# Escorna_CPU_2_01.net
KiCad netlist of a schematic drawn in EAGLE
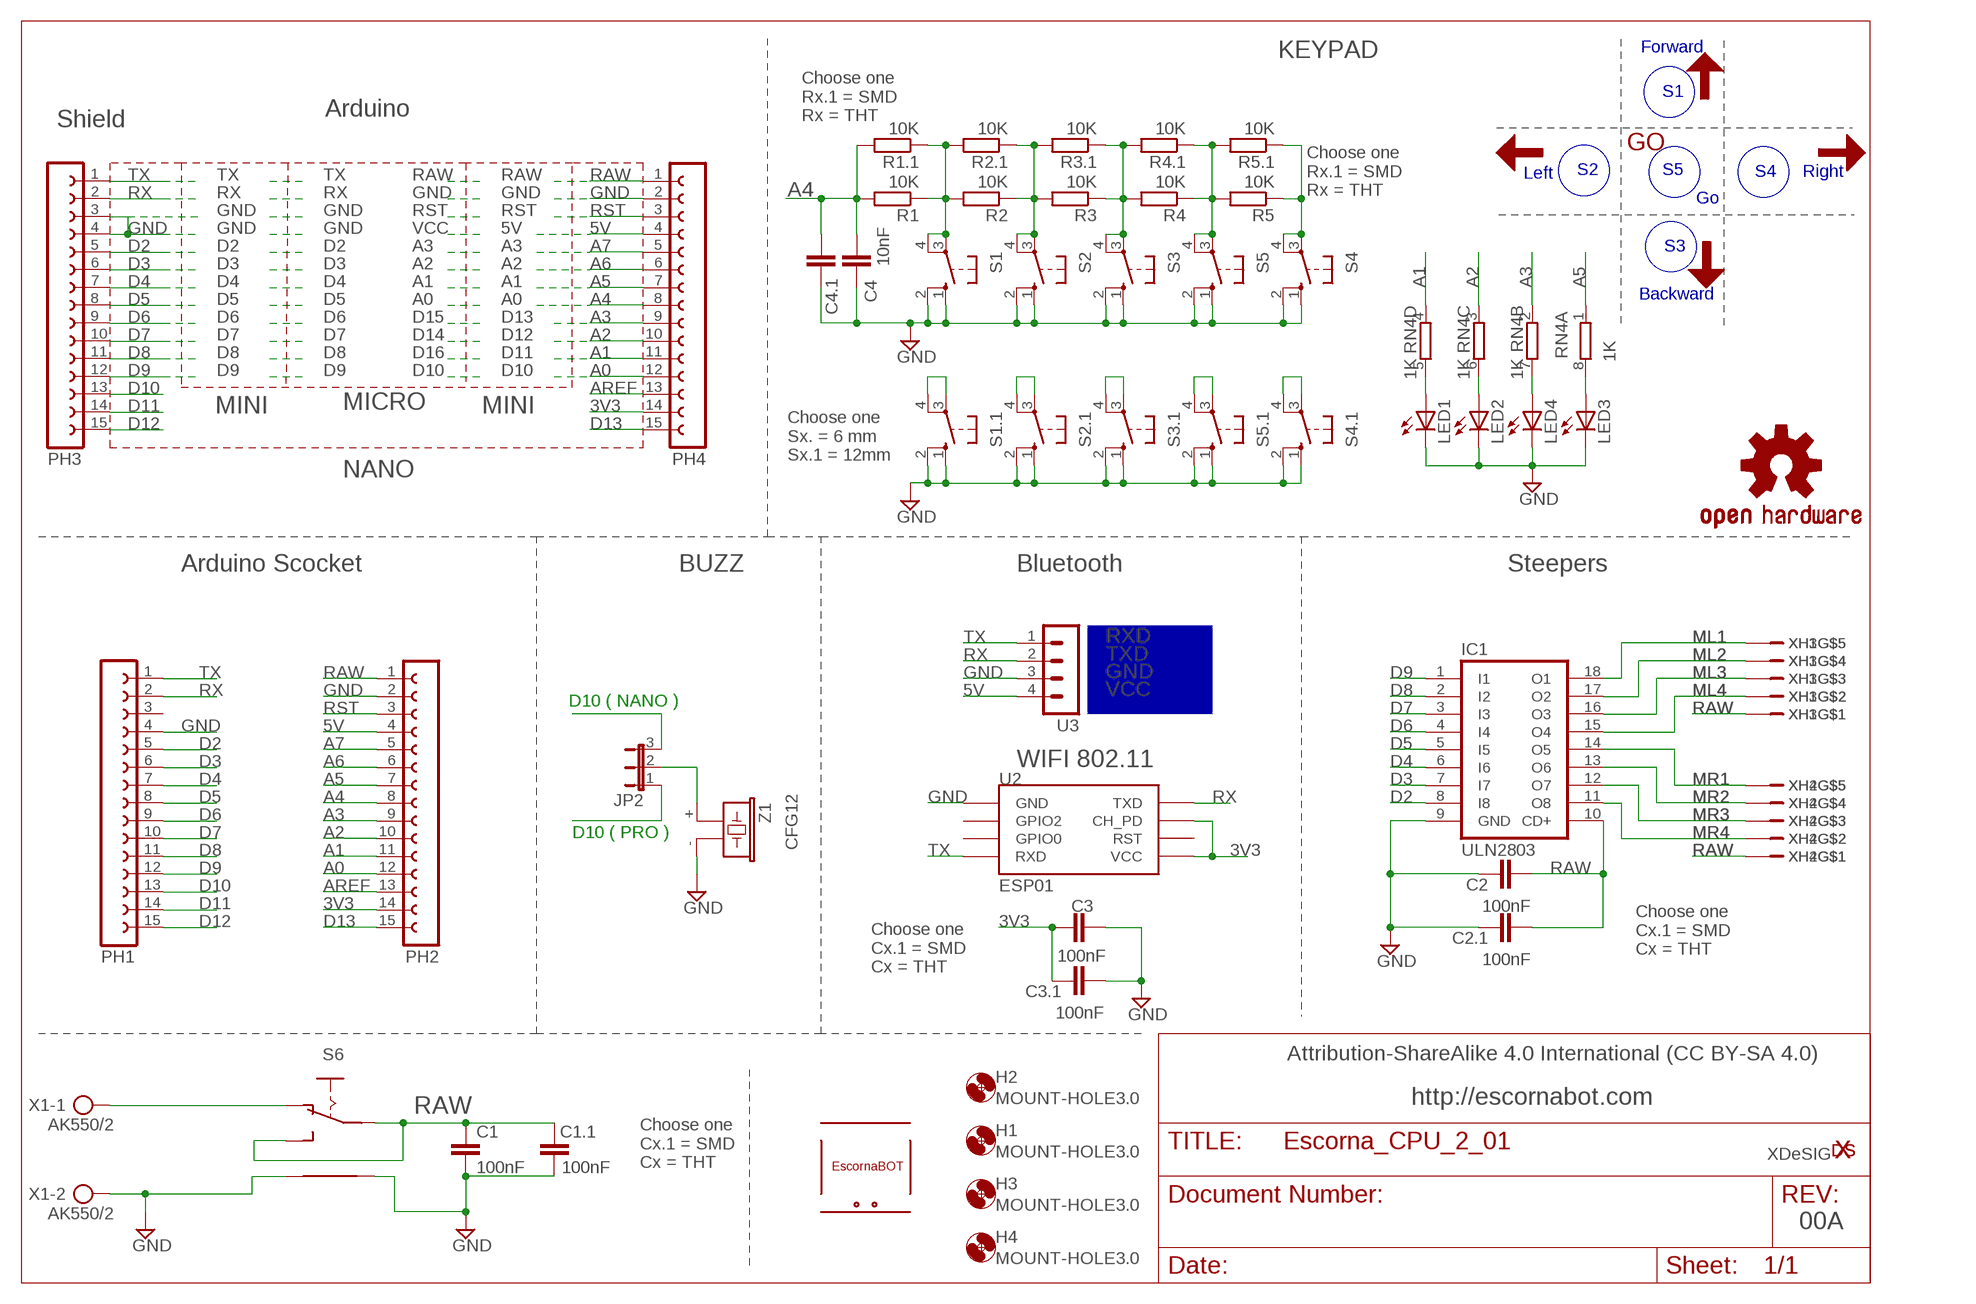
[diagram p0: schematic, sheet 1]

(export (version "E")
  (design (tool "Eeschema 10.0.6"))
  (components
    (comp (ref "C1")
      (value "100nF")
      (footprint "eagle-import:C025-025X050")
      (libsource (lib "eagle-import") (part "C-EU025-025X050"))
    )
    (comp (ref "C1.1")
      (value "100nF")
      (footprint "eagle-import:C0603")
      (libsource (lib "eagle-import") (part "C-EUC0603"))
    )
    (comp (ref "C2")
      (value "100nF")
      (footprint "eagle-import:C025-025X050")
      (libsource (lib "eagle-import") (part "C-EU025-025X050"))
    )
    (comp (ref "C2.1")
      (value "100nF")
      (footprint "eagle-import:C0603")
      (libsource (lib "eagle-import") (part "C-EUC0603"))
    )
    (comp (ref "C3")
      (value "100nF")
      (footprint "eagle-import:C025-025X050")
      (libsource (lib "eagle-import") (part "C-EU025-025X050"))
    )
    (comp (ref "C3.1")
      (value "100nF")
      (footprint "eagle-import:C0603")
      (libsource (lib "eagle-import") (part "C-EUC0603"))
    )
    (comp (ref "C4")
      (value "10nF")
      (footprint "eagle-import:C025-025X050")
      (libsource (lib "eagle-import") (part "C-EU025-025X050"))
    )
    (comp (ref "C4.1")
      (value "10nF")
      (footprint "eagle-import:C0603")
      (libsource (lib "eagle-import") (part "C-EUC0603"))
    )
    (comp (ref "ESC")
      (value "ESCORNABOT")
      (footprint "eagle-import:ESCORNA_PEQUE")
      (libsource (lib "eagle-import") (part "ESCORNABOT"))
    )
    (comp (ref "H1")
      (value "MOUNT-HOLE3.0")
      (footprint "eagle-import:3,0")
      (libsource (lib "eagle-import") (part "MOUNT-HOLE3.0"))
    )
    (comp (ref "H2")
      (value "MOUNT-HOLE3.0")
      (footprint "eagle-import:3,0")
      (libsource (lib "eagle-import") (part "MOUNT-HOLE3.0"))
    )
    (comp (ref "H3")
      (value "MOUNT-HOLE3.0")
      (footprint "eagle-import:3,0")
      (libsource (lib "eagle-import") (part "MOUNT-HOLE3.0"))
    )
    (comp (ref "H4")
      (value "MOUNT-HOLE3.0")
      (footprint "eagle-import:3,0")
      (libsource (lib "eagle-import") (part "MOUNT-HOLE3.0"))
    )
    (comp (ref "IC1")
      (value "ULN2803")
      (footprint "eagle-import:DIL18")
      (libsource (lib "eagle-import") (part "ULN2803A{dblquote}"))
    )
    (comp (ref "JP2")
      (value "JP2E")
      (footprint "eagle-import:JP2")
      (libsource (lib "eagle-import") (part "JP2E"))
    )
    (comp (ref "LED1")
      (value "LED_ESML0603")
      (footprint "eagle-import:LED_SML0603")
      (libsource (lib "eagle-import") (part "LED_ESML0603"))
    )
    (comp (ref "LED2")
      (value "LED_ESML0603")
      (footprint "eagle-import:LED_SML0603")
      (libsource (lib "eagle-import") (part "LED_ESML0603"))
    )
    (comp (ref "LED3")
      (value "LED_ESML0603")
      (footprint "eagle-import:LED_SML0603")
      (libsource (lib "eagle-import") (part "LED_ESML0603"))
    )
    (comp (ref "LED4")
      (value "LED_ESML0603")
      (footprint "eagle-import:LED_SML0603")
      (libsource (lib "eagle-import") (part "LED_ESML0603"))
    )
    (comp (ref "LOGO2")
      (value "OSHW-LOGOS")
      (footprint "eagle-import:OSHW-LOGO-S")
      (libsource (lib "eagle-import") (part "OSHW-LOGOS"))
    )
    (comp (ref "PH1")
      (value "FE15-1")
      (footprint "eagle-import:FE15")
      (libsource (lib "eagle-import") (part "FE15-1"))
    )
    (comp (ref "PH2")
      (value "FE15-1")
      (footprint "eagle-import:FE15")
      (libsource (lib "eagle-import") (part "FE15-1"))
    )
    (comp (ref "PH3")
      (value "FE15-1")
      (footprint "eagle-import:FE15")
      (libsource (lib "eagle-import") (part "FE15-1"))
    )
    (comp (ref "PH4")
      (value "FE15-1")
      (footprint "eagle-import:FE15")
      (libsource (lib "eagle-import") (part "FE15-1"))
    )
    (comp (ref "R1")
      (value "10K")
      (footprint "eagle-import:0204_7")
      (libsource (lib "eagle-import") (part "R-EU_0204/7"))
    )
    (comp (ref "R1.1")
      (value "10K")
      (footprint "eagle-import:R0603")
      (libsource (lib "eagle-import") (part "R-EU_R0603"))
    )
    (comp (ref "R2")
      (value "10K")
      (footprint "eagle-import:0204_7")
      (libsource (lib "eagle-import") (part "R-EU_0204/7"))
    )
    (comp (ref "R2.1")
      (value "10K")
      (footprint "eagle-import:R0603")
      (libsource (lib "eagle-import") (part "R-EU_R0603"))
    )
    (comp (ref "R3")
      (value "10K")
      (footprint "eagle-import:0204_7")
      (libsource (lib "eagle-import") (part "R-EU_0204/7"))
    )
    (comp (ref "R3.1")
      (value "10K")
      (footprint "eagle-import:R0603")
      (libsource (lib "eagle-import") (part "R-EU_R0603"))
    )
    (comp (ref "R4")
      (value "10K")
      (footprint "eagle-import:0204_7")
      (libsource (lib "eagle-import") (part "R-EU_0204/7"))
    )
    (comp (ref "R4.1")
      (value "10K")
      (footprint "eagle-import:R0603")
      (libsource (lib "eagle-import") (part "R-EU_R0603"))
    )
    (comp (ref "R5")
      (value "10K")
      (footprint "eagle-import:0204_7")
      (libsource (lib "eagle-import") (part "R-EU_0204/7"))
    )
    (comp (ref "R5.1")
      (value "10K")
      (footprint "eagle-import:R0603")
      (libsource (lib "eagle-import") (part "R-EU_R0603"))
    )
    (comp (ref "RN4")
      (value "1K")
      (footprint "eagle-import:CAY16")
      (libsource (lib "eagle-import") (part "4R-NCAY16"))
    )
    (comp (ref "S1")
      (value "10-XX")
      (footprint "eagle-import:B3F-10XX")
      (fields (field (name "MPN") "B3F-1000"))
      (libsource (lib "eagle-import") (part "10-XX"))
    )
    (comp (ref "S1.1")
      (value "SWITCH-OMRON_40-XX")
      (footprint "eagle-import:SWITCH-OMRON_B3F40XX_NH")
      (libsource (lib "eagle-import") (part "SWITCH-OMRON_40-XX"))
    )
    (comp (ref "S2")
      (value "10-XX")
      (footprint "eagle-import:B3F-10XX")
      (fields (field (name "MPN") "B3F-1000"))
      (libsource (lib "eagle-import") (part "10-XX"))
    )
    (comp (ref "S2.1")
      (value "SWITCH-OMRON_40-XX")
      (footprint "eagle-import:SWITCH-OMRON_B3F40XX_NH")
      (libsource (lib "eagle-import") (part "SWITCH-OMRON_40-XX"))
    )
    (comp (ref "S3")
      (value "10-XX")
      (footprint "eagle-import:B3F-10XX")
      (fields (field (name "MPN") "B3F-1000"))
      (libsource (lib "eagle-import") (part "10-XX"))
    )
    (comp (ref "S3.1")
      (value "SWITCH-OMRON_40-XX")
      (footprint "eagle-import:SWITCH-OMRON_B3F40XX_NH")
      (libsource (lib "eagle-import") (part "SWITCH-OMRON_40-XX"))
    )
    (comp (ref "S4")
      (value "10-XX")
      (footprint "eagle-import:B3F-10XX")
      (fields (field (name "MPN") "B3F-1000"))
      (libsource (lib "eagle-import") (part "10-XX"))
    )
    (comp (ref "S4.1")
      (value "SWITCH-OMRON_40-XX")
      (footprint "eagle-import:SWITCH-OMRON_B3F40XX_NH")
      (libsource (lib "eagle-import") (part "SWITCH-OMRON_40-XX"))
    )
    (comp (ref "S5")
      (value "10-XX")
      (footprint "eagle-import:B3F-10XX")
      (fields (field (name "MPN") "B3F-1000"))
      (libsource (lib "eagle-import") (part "10-XX"))
    )
    (comp (ref "S5.1")
      (value "SWITCH-OMRON_40-XX")
      (footprint "eagle-import:SWITCH-OMRON_B3F40XX_NH")
      (libsource (lib "eagle-import") (part "SWITCH-OMRON_40-XX"))
    )
    (comp (ref "S6")
      (value "SK12F14D")
      (footprint "eagle-import:SK-12D07")
      (libsource (lib "eagle-import") (part "SK12F14D"))
    )
    (comp (ref "U$1")
      (value "FRECHA")
      (footprint "eagle-import:FRECHA")
      (libsource (lib "eagle-import") (part "FRECHA"))
    )
    (comp (ref "U$2")
      (value "GO")
      (footprint "eagle-import:VALE")
      (libsource (lib "eagle-import") (part "GO"))
    )
    (comp (ref "U$3")
      (value "FRECHA")
      (footprint "eagle-import:FRECHA")
      (libsource (lib "eagle-import") (part "FRECHA"))
    )
    (comp (ref "U$6")
      (value "FRECHA")
      (footprint "eagle-import:FRECHA")
      (libsource (lib "eagle-import") (part "FRECHA"))
    )
    (comp (ref "U$11")
      (value "FRECHA")
      (footprint "eagle-import:FRECHA")
      (libsource (lib "eagle-import") (part "FRECHA"))
    )
    (comp (ref "U$12")
      (value "XDESIG_XDESIG21")
      (footprint "eagle-import:XDESIG_XDESIG")
      (libsource (lib "eagle-import") (part "XDESIG_XDESIG21"))
    )
    (comp (ref "U2")
      (value "ESP01")
      (footprint "eagle-import:ESP01")
      (libsource (lib "eagle-import") (part "ESP01"))
    )
    (comp (ref "U3")
      (value "MA04-1")
      (footprint "eagle-import:MA04-1")
      (libsource (lib "eagle-import") (part "MA04-1"))
    )
    (comp (ref "X1")
      (value "AK550/2")
      (footprint "eagle-import:AK550_2")
      (libsource (lib "eagle-import") (part "AK550/2"))
    )
    (comp (ref "XDS1")
      (value "XDESIG")
      (footprint "eagle-import:XDESIG_CU_2")
      (libsource (lib "eagle-import") (part "XDESIG"))
    )
    (comp (ref "XH1")
      (value "B5B-XH-A")
      (footprint "eagle-import:B5B-XH-A")
      (libsource (lib "eagle-import") (part "B5B-XH-A"))
    )
    (comp (ref "XH2")
      (value "B5B-XH-A")
      (footprint "eagle-import:B5B-XH-A")
      (libsource (lib "eagle-import") (part "B5B-XH-A"))
    )
    (comp (ref "XH3")
      (value "B5B-XH-A")
      (footprint "eagle-import:B5B-XH-A")
      (libsource (lib "eagle-import") (part "B5B-XH-A"))
    )
    (comp (ref "XH4")
      (value "B5B-XH-A")
      (footprint "eagle-import:B5B-XH-A")
      (libsource (lib "eagle-import") (part "B5B-XH-A"))
    )
    (comp (ref "Z1")
      (value "CFG12")
      (footprint "eagle-import:F_CM12P")
      (libsource (lib "eagle-import") (part "F/CM12P"))
    )
  )
  (nets
    (net (code "1") (name "/3V3") (class "Default")
      (node (ref "C3") (pin "1") (pinfunction "1_1") (pintype "passive"))
      (node (ref "C3.1") (pin "1") (pinfunction "1_1") (pintype "passive"))
      (node (ref "PH2") (pin "14") (pinfunction "14_14") (pintype "passive"))
      (node (ref "PH4") (pin "14") (pinfunction "14_14") (pintype "passive"))
      (node (ref "U2") (pin "CH_PD") (pinfunction "CH_PD_CH_PD") (pintype "bidirectional"))
      (node (ref "U2") (pin "VCC") (pinfunction "VCC_VCC") (pintype "bidirectional"))
    )
    (net (code "2") (name "/5V") (class "Default")
      (node (ref "PH2") (pin "4") (pinfunction "4_4") (pintype "passive"))
      (node (ref "PH4") (pin "4") (pinfunction "4_4") (pintype "passive"))
      (node (ref "U3") (pin "4") (pinfunction "4_4") (pintype "passive"))
    )
    (net (code "3") (name "/A0") (class "Default")
      (node (ref "JP2") (pin "1") (pinfunction "1_1") (pintype "passive"))
      (node (ref "PH2") (pin "12") (pinfunction "12_12") (pintype "passive"))
      (node (ref "PH4") (pin "12") (pinfunction "12_12") (pintype "passive"))
    )
    (net (code "4") (name "/A1") (class "Default")
      (node (ref "PH2") (pin "11") (pinfunction "11_11") (pintype "passive"))
      (node (ref "PH4") (pin "11") (pinfunction "11_11") (pintype "passive"))
      (node (ref "RN4") (pin "4") (pinfunction "1_4") (pintype "passive"))
    )
    (net (code "5") (name "/A2") (class "Default")
      (node (ref "PH2") (pin "10") (pinfunction "10_10") (pintype "passive"))
      (node (ref "PH4") (pin "10") (pinfunction "10_10") (pintype "passive"))
      (node (ref "RN4") (pin "3") (pinfunction "1_3") (pintype "passive"))
    )
    (net (code "6") (name "/A3") (class "Default")
      (node (ref "PH2") (pin "9") (pinfunction "9_9") (pintype "passive"))
      (node (ref "PH4") (pin "9") (pinfunction "9_9") (pintype "passive"))
      (node (ref "RN4") (pin "2") (pinfunction "1_2") (pintype "passive"))
    )
    (net (code "7") (name "/A4") (class "Default")
      (node (ref "C4") (pin "2") (pinfunction "2_2") (pintype "passive"))
      (node (ref "C4.1") (pin "2") (pinfunction "2_2") (pintype "passive"))
      (node (ref "PH2") (pin "8") (pinfunction "8_8") (pintype "passive"))
      (node (ref "PH4") (pin "8") (pinfunction "8_8") (pintype "passive"))
      (node (ref "R1") (pin "2") (pinfunction "2_2") (pintype "passive"))
      (node (ref "R1.1") (pin "2") (pinfunction "2_2") (pintype "passive"))
    )
    (net (code "8") (name "/A5") (class "Default")
      (node (ref "PH2") (pin "7") (pinfunction "7_7") (pintype "passive"))
      (node (ref "PH4") (pin "7") (pinfunction "7_7") (pintype "passive"))
      (node (ref "RN4") (pin "1") (pinfunction "1_1") (pintype "passive"))
    )
    (net (code "9") (name "/A6") (class "Default")
      (node (ref "PH2") (pin "6") (pinfunction "6_6") (pintype "passive"))
      (node (ref "PH4") (pin "6") (pinfunction "6_6") (pintype "passive"))
    )
    (net (code "10") (name "/A7") (class "Default")
      (node (ref "PH2") (pin "5") (pinfunction "5_5") (pintype "passive"))
      (node (ref "PH4") (pin "5") (pinfunction "5_5") (pintype "passive"))
    )
    (net (code "11") (name "/AREF") (class "Default")
      (node (ref "PH2") (pin "13") (pinfunction "13_13") (pintype "passive"))
      (node (ref "PH4") (pin "13") (pinfunction "13_13") (pintype "passive"))
    )
    (net (code "12") (name "/D2") (class "Default")
      (node (ref "IC1") (pin "8") (pinfunction "I8_8") (pintype "input"))
      (node (ref "PH1") (pin "5") (pinfunction "5_5") (pintype "passive"))
      (node (ref "PH3") (pin "5") (pinfunction "5_5") (pintype "passive"))
    )
    (net (code "13") (name "/D3") (class "Default")
      (node (ref "IC1") (pin "7") (pinfunction "I7_7") (pintype "input"))
      (node (ref "PH1") (pin "6") (pinfunction "6_6") (pintype "passive"))
      (node (ref "PH3") (pin "6") (pinfunction "6_6") (pintype "passive"))
    )
    (net (code "14") (name "/D4") (class "Default")
      (node (ref "IC1") (pin "6") (pinfunction "I6_6") (pintype "input"))
      (node (ref "PH1") (pin "7") (pinfunction "7_7") (pintype "passive"))
      (node (ref "PH3") (pin "7") (pinfunction "7_7") (pintype "passive"))
    )
    (net (code "15") (name "/D5") (class "Default")
      (node (ref "IC1") (pin "5") (pinfunction "I5_5") (pintype "input"))
      (node (ref "PH1") (pin "8") (pinfunction "8_8") (pintype "passive"))
      (node (ref "PH3") (pin "8") (pinfunction "8_8") (pintype "passive"))
    )
    (net (code "16") (name "/D6") (class "Default")
      (node (ref "IC1") (pin "4") (pinfunction "I4_4") (pintype "input"))
      (node (ref "PH1") (pin "9") (pinfunction "9_9") (pintype "passive"))
      (node (ref "PH3") (pin "9") (pinfunction "9_9") (pintype "passive"))
    )
    (net (code "17") (name "/D7") (class "Default")
      (node (ref "IC1") (pin "3") (pinfunction "I3_3") (pintype "input"))
      (node (ref "PH1") (pin "10") (pinfunction "10_10") (pintype "passive"))
      (node (ref "PH3") (pin "10") (pinfunction "10_10") (pintype "passive"))
    )
    (net (code "18") (name "/D8") (class "Default")
      (node (ref "IC1") (pin "2") (pinfunction "I2_2") (pintype "input"))
      (node (ref "PH1") (pin "11") (pinfunction "11_11") (pintype "passive"))
      (node (ref "PH3") (pin "11") (pinfunction "11_11") (pintype "passive"))
    )
    (net (code "19") (name "/D9") (class "Default")
      (node (ref "IC1") (pin "1") (pinfunction "I1_1") (pintype "input"))
      (node (ref "PH1") (pin "12") (pinfunction "12_12") (pintype "passive"))
      (node (ref "PH3") (pin "12") (pinfunction "12_12") (pintype "passive"))
    )
    (net (code "20") (name "/D10") (class "Default")
      (node (ref "JP2") (pin "3") (pinfunction "3_3") (pintype "passive"))
      (node (ref "PH1") (pin "13") (pinfunction "13_13") (pintype "passive"))
      (node (ref "PH3") (pin "13") (pinfunction "13_13") (pintype "passive"))
    )
    (net (code "21") (name "/D11") (class "Default")
      (node (ref "PH1") (pin "14") (pinfunction "14_14") (pintype "passive"))
      (node (ref "PH3") (pin "14") (pinfunction "14_14") (pintype "passive"))
    )
    (net (code "22") (name "/D12") (class "Default")
      (node (ref "PH1") (pin "15") (pinfunction "15_15") (pintype "passive"))
      (node (ref "PH3") (pin "15") (pinfunction "15_15") (pintype "passive"))
    )
    (net (code "23") (name "/D13") (class "Default")
      (node (ref "PH2") (pin "15") (pinfunction "15_15") (pintype "passive"))
      (node (ref "PH4") (pin "15") (pinfunction "15_15") (pintype "passive"))
    )
    (net (code "24") (name "/ML1") (class "Default")
      (node (ref "IC1") (pin "18") (pinfunction "O1_18") (pintype "open_collector"))
      (node (ref "XH1") (pin "P$5") (pinfunction "1_P$5") (pintype "passive"))
      (node (ref "XH3") (pin "P$5") (pinfunction "1_P$5") (pintype "passive"))
    )
    (net (code "25") (name "/ML2") (class "Default")
      (node (ref "IC1") (pin "17") (pinfunction "O2_17") (pintype "open_collector"))
      (node (ref "XH1") (pin "P$4") (pinfunction "1_P$4") (pintype "passive"))
      (node (ref "XH3") (pin "P$4") (pinfunction "1_P$4") (pintype "passive"))
    )
    (net (code "26") (name "/ML3") (class "Default")
      (node (ref "IC1") (pin "16") (pinfunction "O3_16") (pintype "open_collector"))
      (node (ref "XH1") (pin "P$3") (pinfunction "1_P$3") (pintype "passive"))
      (node (ref "XH3") (pin "P$3") (pinfunction "1_P$3") (pintype "passive"))
    )
    (net (code "27") (name "/ML4") (class "Default")
      (node (ref "IC1") (pin "15") (pinfunction "O4_15") (pintype "open_collector"))
      (node (ref "XH1") (pin "P$2") (pinfunction "1_P$2") (pintype "passive"))
      (node (ref "XH3") (pin "P$2") (pinfunction "1_P$2") (pintype "passive"))
    )
    (net (code "28") (name "/MR1") (class "Default")
      (node (ref "IC1") (pin "14") (pinfunction "O5_14") (pintype "open_collector"))
      (node (ref "XH2") (pin "P$5") (pinfunction "1_P$5") (pintype "passive"))
      (node (ref "XH4") (pin "P$5") (pinfunction "1_P$5") (pintype "passive"))
    )
    (net (code "29") (name "/MR2") (class "Default")
      (node (ref "IC1") (pin "13") (pinfunction "O6_13") (pintype "open_collector"))
      (node (ref "XH2") (pin "P$4") (pinfunction "1_P$4") (pintype "passive"))
      (node (ref "XH4") (pin "P$4") (pinfunction "1_P$4") (pintype "passive"))
    )
    (net (code "30") (name "/MR3") (class "Default")
      (node (ref "IC1") (pin "12") (pinfunction "O7_12") (pintype "open_collector"))
      (node (ref "XH2") (pin "P$3") (pinfunction "1_P$3") (pintype "passive"))
      (node (ref "XH4") (pin "P$3") (pinfunction "1_P$3") (pintype "passive"))
    )
    (net (code "31") (name "/MR4") (class "Default")
      (node (ref "IC1") (pin "11") (pinfunction "O8_11") (pintype "open_collector"))
      (node (ref "XH2") (pin "P$2") (pinfunction "1_P$2") (pintype "passive"))
      (node (ref "XH4") (pin "P$2") (pinfunction "1_P$2") (pintype "passive"))
    )
    (net (code "32") (name "/RAW") (class "Default")
      (node (ref "C1") (pin "1") (pinfunction "1_1") (pintype "passive"))
      (node (ref "C1.1") (pin "2") (pinfunction "2_2") (pintype "passive"))
      (node (ref "C2") (pin "2") (pinfunction "2_2") (pintype "passive"))
      (node (ref "C2.1") (pin "2") (pinfunction "2_2") (pintype "passive"))
      (node (ref "IC1") (pin "10") (pinfunction "CD+_10") (pintype "passive"))
      (node (ref "PH2") (pin "1") (pinfunction "1_1") (pintype "passive"))
      (node (ref "PH4") (pin "1") (pinfunction "1_1") (pintype "passive"))
      (node (ref "S6") (pin "P$1") (pinfunction "P_P$1") (pintype "passive"))
      (node (ref "S6") (pin "P$3") (pinfunction "S_P$3") (pintype "passive"))
      (node (ref "XH1") (pin "P$1") (pinfunction "1_P$1") (pintype "passive"))
      (node (ref "XH2") (pin "P$1") (pinfunction "1_P$1") (pintype "passive"))
      (node (ref "XH3") (pin "P$1") (pinfunction "1_P$1") (pintype "passive"))
      (node (ref "XH4") (pin "P$1") (pinfunction "1_P$1") (pintype "passive"))
    )
    (net (code "33") (name "/RST") (class "Default")
      (node (ref "PH2") (pin "3") (pinfunction "3_3") (pintype "passive"))
      (node (ref "PH4") (pin "3") (pinfunction "3_3") (pintype "passive"))
    )
    (net (code "34") (name "/RX") (class "Default")
      (node (ref "PH1") (pin "2") (pinfunction "2_2") (pintype "passive"))
      (node (ref "PH3") (pin "2") (pinfunction "2_2") (pintype "passive"))
      (node (ref "U2") (pin "TX") (pinfunction "TXD_TX") (pintype "bidirectional"))
      (node (ref "U3") (pin "2") (pinfunction "2_2") (pintype "passive"))
    )
    (net (code "35") (name "/S1") (class "Default")
      (node (ref "R1") (pin "1") (pinfunction "1_1") (pintype "passive"))
      (node (ref "R1.1") (pin "1") (pinfunction "1_1") (pintype "passive"))
      (node (ref "R2") (pin "2") (pinfunction "2_2") (pintype "passive"))
      (node (ref "R2.1") (pin "2") (pinfunction "2_2") (pintype "passive"))
      (node (ref "S1") (pin "3") (pinfunction "P_3") (pintype "passive"))
      (node (ref "S1") (pin "4") (pinfunction "P1_4") (pintype "passive"))
      (node (ref "S1.1") (pin "3") (pinfunction "P_3") (pintype "passive"))
      (node (ref "S1.1") (pin "4") (pinfunction "P1_4") (pintype "passive"))
    )
    (net (code "36") (name "/S2") (class "Default")
      (node (ref "R2") (pin "1") (pinfunction "1_1") (pintype "passive"))
      (node (ref "R2.1") (pin "1") (pinfunction "1_1") (pintype "passive"))
      (node (ref "R3") (pin "2") (pinfunction "2_2") (pintype "passive"))
      (node (ref "R3.1") (pin "2") (pinfunction "2_2") (pintype "passive"))
      (node (ref "S2") (pin "3") (pinfunction "P_3") (pintype "passive"))
      (node (ref "S2") (pin "4") (pinfunction "P1_4") (pintype "passive"))
      (node (ref "S2.1") (pin "3") (pinfunction "P_3") (pintype "passive"))
      (node (ref "S2.1") (pin "4") (pinfunction "P1_4") (pintype "passive"))
    )
    (net (code "37") (name "/S3") (class "Default")
      (node (ref "R3") (pin "1") (pinfunction "1_1") (pintype "passive"))
      (node (ref "R3.1") (pin "1") (pinfunction "1_1") (pintype "passive"))
      (node (ref "R4") (pin "2") (pinfunction "2_2") (pintype "passive"))
      (node (ref "R4.1") (pin "2") (pinfunction "2_2") (pintype "passive"))
      (node (ref "S3") (pin "3") (pinfunction "P_3") (pintype "passive"))
      (node (ref "S3") (pin "4") (pinfunction "P1_4") (pintype "passive"))
      (node (ref "S3.1") (pin "3") (pinfunction "P_3") (pintype "passive"))
      (node (ref "S3.1") (pin "4") (pinfunction "P1_4") (pintype "passive"))
    )
    (net (code "38") (name "/S4") (class "Default")
      (node (ref "R4") (pin "1") (pinfunction "1_1") (pintype "passive"))
      (node (ref "R4.1") (pin "1") (pinfunction "1_1") (pintype "passive"))
      (node (ref "R5") (pin "2") (pinfunction "2_2") (pintype "passive"))
      (node (ref "R5.1") (pin "2") (pinfunction "2_2") (pintype "passive"))
      (node (ref "S5") (pin "3") (pinfunction "P_3") (pintype "passive"))
      (node (ref "S5") (pin "4") (pinfunction "P1_4") (pintype "passive"))
      (node (ref "S5.1") (pin "3") (pinfunction "P_3") (pintype "passive"))
      (node (ref "S5.1") (pin "4") (pinfunction "P1_4") (pintype "passive"))
    )
    (net (code "39") (name "/S5") (class "Default")
      (node (ref "R5") (pin "1") (pinfunction "1_1") (pintype "passive"))
      (node (ref "R5.1") (pin "1") (pinfunction "1_1") (pintype "passive"))
      (node (ref "S4") (pin "3") (pinfunction "P_3") (pintype "passive"))
      (node (ref "S4") (pin "4") (pinfunction "P1_4") (pintype "passive"))
      (node (ref "S4.1") (pin "3") (pinfunction "P_3") (pintype "passive"))
      (node (ref "S4.1") (pin "4") (pinfunction "P1_4") (pintype "passive"))
    )
    (net (code "40") (name "/TX") (class "Default")
      (node (ref "PH1") (pin "1") (pinfunction "1_1") (pintype "passive"))
      (node (ref "PH3") (pin "1") (pinfunction "1_1") (pintype "passive"))
      (node (ref "U2") (pin "RX") (pinfunction "RXD_RX") (pintype "bidirectional"))
      (node (ref "U3") (pin "1") (pinfunction "1_1") (pintype "passive"))
    )
    (net (code "41") (name "GND") (class "Default")
      (node (ref "C1") (pin "2") (pinfunction "2_2") (pintype "passive"))
      (node (ref "C1.1") (pin "1") (pinfunction "1_1") (pintype "passive"))
      (node (ref "C2") (pin "1") (pinfunction "1_1") (pintype "passive"))
      (node (ref "C2.1") (pin "1") (pinfunction "1_1") (pintype "passive"))
      (node (ref "C3") (pin "2") (pinfunction "2_2") (pintype "passive"))
      (node (ref "C3.1") (pin "2") (pinfunction "2_2") (pintype "passive"))
      (node (ref "C4") (pin "1") (pinfunction "1_1") (pintype "passive"))
      (node (ref "C4.1") (pin "1") (pinfunction "1_1") (pintype "passive"))
      (node (ref "IC1") (pin "9") (pinfunction "GND_9") (pintype "power_in"))
      (node (ref "LED1") (pin "C") (pinfunction "C_C") (pintype "passive"))
      (node (ref "LED2") (pin "C") (pinfunction "C_C") (pintype "passive"))
      (node (ref "LED3") (pin "C") (pinfunction "C_C") (pintype "passive"))
      (node (ref "LED4") (pin "C") (pinfunction "C_C") (pintype "passive"))
      (node (ref "PH1") (pin "4") (pinfunction "4_4") (pintype "passive"))
      (node (ref "PH2") (pin "2") (pinfunction "2_2") (pintype "passive"))
      (node (ref "PH3") (pin "3") (pinfunction "3_3") (pintype "passive"))
      (node (ref "PH3") (pin "4") (pinfunction "4_4") (pintype "passive"))
      (node (ref "PH4") (pin "2") (pinfunction "2_2") (pintype "passive"))
      (node (ref "S1") (pin "1") (pinfunction "S_1") (pintype "passive"))
      (node (ref "S1") (pin "2") (pinfunction "S1_2") (pintype "passive"))
      (node (ref "S1.1") (pin "1") (pinfunction "S_1") (pintype "passive"))
      (node (ref "S1.1") (pin "2") (pinfunction "S1_2") (pintype "passive"))
      (node (ref "S2") (pin "1") (pinfunction "S_1") (pintype "passive"))
      (node (ref "S2") (pin "2") (pinfunction "S1_2") (pintype "passive"))
      (node (ref "S2.1") (pin "1") (pinfunction "S_1") (pintype "passive"))
      (node (ref "S2.1") (pin "2") (pinfunction "S1_2") (pintype "passive"))
      (node (ref "S3") (pin "1") (pinfunction "S_1") (pintype "passive"))
      (node (ref "S3") (pin "2") (pinfunction "S1_2") (pintype "passive"))
      (node (ref "S3.1") (pin "1") (pinfunction "S_1") (pintype "passive"))
      (node (ref "S3.1") (pin "2") (pinfunction "S1_2") (pintype "passive"))
      (node (ref "S4") (pin "1") (pinfunction "S_1") (pintype "passive"))
      (node (ref "S4") (pin "2") (pinfunction "S1_2") (pintype "passive"))
      (node (ref "S4.1") (pin "1") (pinfunction "S_1") (pintype "passive"))
      (node (ref "S4.1") (pin "2") (pinfunction "S1_2") (pintype "passive"))
      (node (ref "S5") (pin "1") (pinfunction "S_1") (pintype "passive"))
      (node (ref "S5") (pin "2") (pinfunction "S1_2") (pintype "passive"))
      (node (ref "S5.1") (pin "1") (pinfunction "S_1") (pintype "passive"))
      (node (ref "S5.1") (pin "2") (pinfunction "S1_2") (pintype "passive"))
      (node (ref "S6") (pin "P$4") (pinfunction "P$1_P$4") (pintype "passive"))
      (node (ref "S6") (pin "P$5") (pinfunction "P$2_P$5") (pintype "bidirectional"))
      (node (ref "U2") (pin "GND") (pinfunction "GND_GND") (pintype "bidirectional"))
      (node (ref "U3") (pin "3") (pinfunction "3_3") (pintype "passive"))
      (node (ref "X1") (pin "2") (pinfunction "KL_2") (pintype "passive"))
      (node (ref "Z1") (pin "-") (pinfunction "2_-") (pintype "passive"))
    )
    (net (code "42") (name "Net-(RN4A-2)") (class "Default")
      (node (ref "LED3") (pin "A") (pinfunction "A_A") (pintype "passive"))
      (node (ref "RN4") (pin "8") (pinfunction "2_8") (pintype "passive"))
    )
    (net (code "43") (name "Net-(RN4B-2)") (class "Default")
      (node (ref "LED4") (pin "A") (pinfunction "A_A") (pintype "passive"))
      (node (ref "RN4") (pin "7") (pinfunction "2_7") (pintype "passive"))
    )
    (net (code "44") (name "Net-(RN4C-2)") (class "Default")
      (node (ref "LED2") (pin "A") (pinfunction "A_A") (pintype "passive"))
      (node (ref "RN4") (pin "6") (pinfunction "2_6") (pintype "passive"))
    )
    (net (code "45") (name "Net-(RN4D-2)") (class "Default")
      (node (ref "LED1") (pin "A") (pinfunction "A_A") (pintype "passive"))
      (node (ref "RN4") (pin "5") (pinfunction "2_5") (pintype "passive"))
    )
    (net (code "46") (name "Net-(S6-O)") (class "Default")
      (node (ref "S6") (pin "P$2") (pinfunction "O_P$2") (pintype "passive"))
      (node (ref "X1") (pin "1") (pinfunction "KL_1") (pintype "passive"))
    )
    (net (code "47") (name "Net-(Z1-1)") (class "Default")
      (node (ref "JP2") (pin "2") (pinfunction "2_2") (pintype "passive"))
      (node (ref "Z1") (pin "+") (pinfunction "1_+") (pintype "passive"))
    )
    (net (code "48") (name "unconnected-(PH1-Pad3)") (class "Default")
      (node (ref "PH1") (pin "3") (pinfunction "3_3") (pintype "passive"))
    )
    (net (code "49") (name "unconnected-(U2-PadGPIO0)") (class "Default")
      (node (ref "U2") (pin "GPIO0") (pinfunction "GPIO0_GPIO0") (pintype "bidirectional"))
    )
    (net (code "50") (name "unconnected-(U2-PadGPIO2)") (class "Default")
      (node (ref "U2") (pin "GPIO2") (pinfunction "GPIO2_GPIO2") (pintype "bidirectional"))
    )
    (net (code "51") (name "unconnected-(U2-PadRST)") (class "Default")
      (node (ref "U2") (pin "RST") (pinfunction "RST_RST") (pintype "bidirectional"))
    )
  )
)
